# MainCircuit.net
KiCad netlist of a schematic drawn in Altium Designer
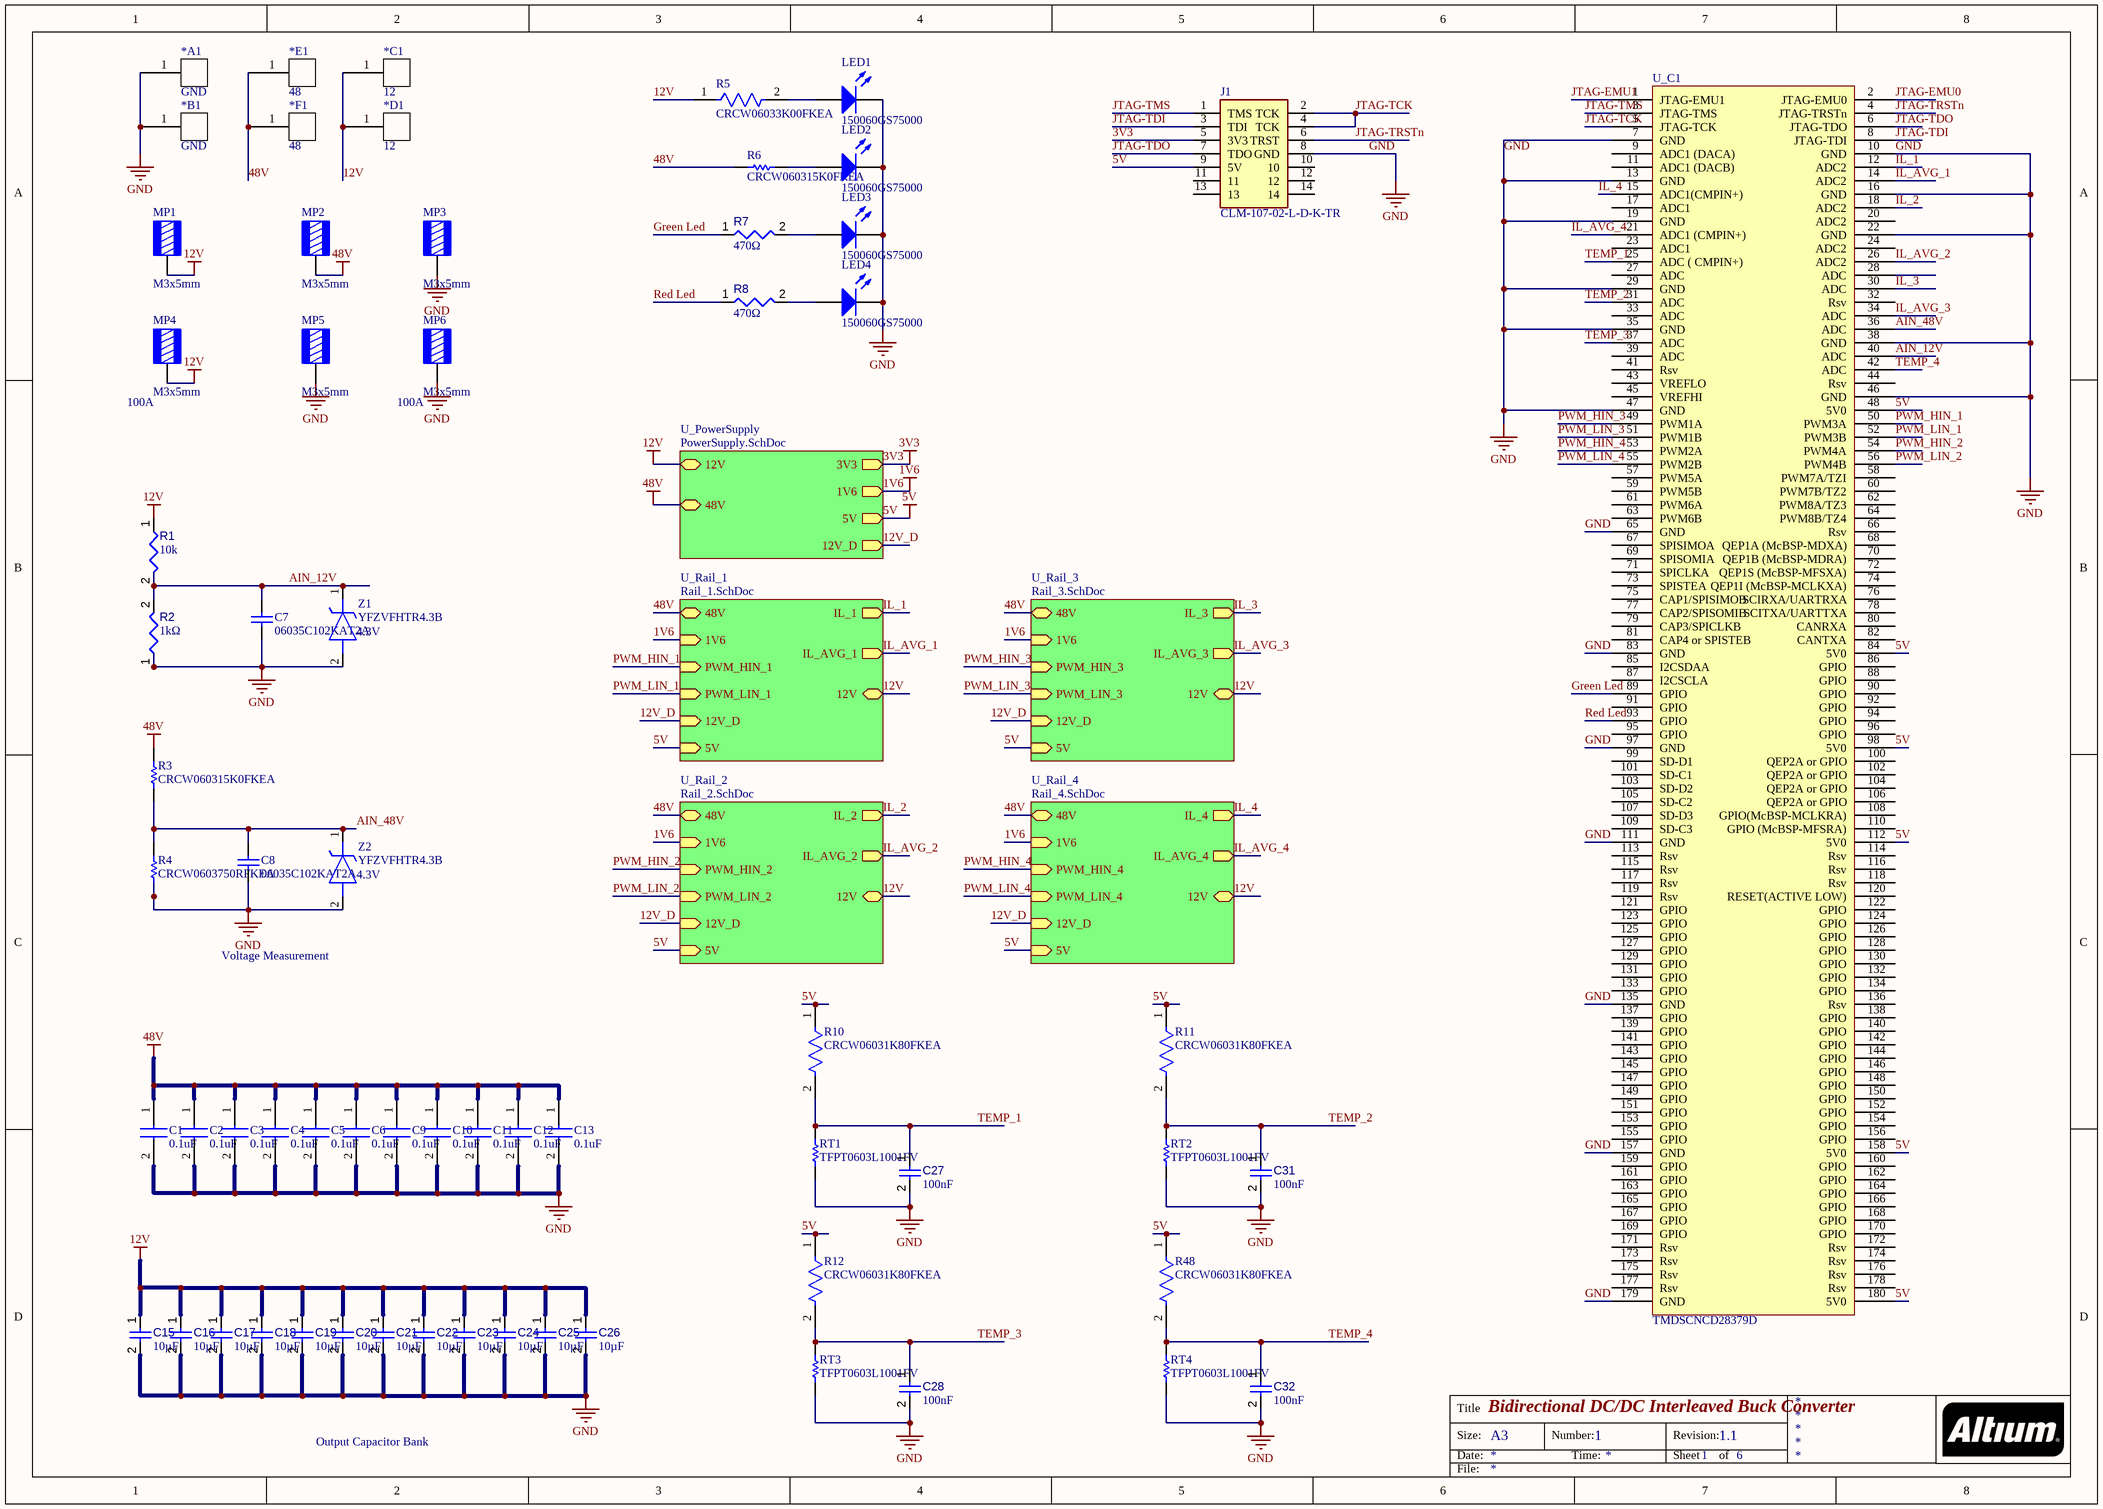
[diagram p0: MainCircuit.SchDoc]

(export (version "E")
  (design (tool "Eeschema 10.0.6"))
  (components
    (comp (ref "*A1")
      (value "GND")
      (description "Power Pad for Ground and Supply")
      (libsource (lib "University of Paderborn") (part "Power Pad"))
    )
    (comp (ref "*B1")
      (value "GND")
      (description "Power Pad for Ground and Supply")
      (libsource (lib "University of Paderborn") (part "Power Pad"))
    )
    (comp (ref "*C1")
      (value "12")
      (description "Power Pad for Ground and Supply")
      (libsource (lib "University of Paderborn") (part "Power Pad"))
    )
    (comp (ref "*D1")
      (value "12")
      (description "Power Pad for Ground and Supply")
      (libsource (lib "University of Paderborn") (part "Power Pad"))
    )
    (comp (ref "*E1")
      (value "48")
      (description "Power Pad for Ground and Supply")
      (libsource (lib "University of Paderborn") (part "Power Pad"))
    )
    (comp (ref "*F1")
      (value "48")
      (description "Power Pad for Ground and Supply")
      (libsource (lib "University of Paderborn") (part "Power Pad"))
    )
    (comp (ref "C1")
      (value "0.1uF")
      (footprint "SamacSys:CAPC1608X90N")
      (description "Capacitor")
      (fields
        (field (name "MANUFACTURER_PART_NUMBER") "06031C104K4T2A")
        (field (name "MOUSER PART NUMBER") "581-06031C104K4T2A")
      )
      (libsource (lib "*") (part "06031C104K4T2A"))
    )
    (comp (ref "C2")
      (value "0.1uF")
      (footprint "SamacSys:CAPC1608X90N")
      (description "Capacitor")
      (fields
        (field (name "MANUFACTURER_PART_NUMBER") "06031C104K4T2A")
        (field (name "MOUSER PART NUMBER") "581-06031C104K4T2A")
      )
      (libsource (lib "*") (part "06031C104K4T2A"))
    )
    (comp (ref "C3")
      (value "0.1uF")
      (footprint "SamacSys:CAPC1608X90N")
      (description "Capacitor")
      (fields
        (field (name "MANUFACTURER_PART_NUMBER") "06031C104K4T2A")
        (field (name "MOUSER PART NUMBER") "581-06031C104K4T2A")
      )
      (libsource (lib "*") (part "06031C104K4T2A"))
    )
    (comp (ref "C4")
      (value "0.1uF")
      (footprint "SamacSys:CAPC1608X90N")
      (description "Capacitor")
      (fields
        (field (name "MANUFACTURER_PART_NUMBER") "06031C104K4T2A")
        (field (name "MOUSER PART NUMBER") "581-06031C104K4T2A")
      )
      (libsource (lib "*") (part "06031C104K4T2A"))
    )
    (comp (ref "C5")
      (value "0.1uF")
      (footprint "SamacSys:CAPC1608X90N")
      (description "Capacitor")
      (fields
        (field (name "MANUFACTURER_PART_NUMBER") "06031C104K4T2A")
        (field (name "MOUSER PART NUMBER") "581-06031C104K4T2A")
      )
      (libsource (lib "*") (part "06031C104K4T2A"))
    )
    (comp (ref "C6")
      (value "0.1uF")
      (footprint "SamacSys:CAPC1608X90N")
      (description "Capacitor")
      (fields
        (field (name "MANUFACTURER_PART_NUMBER") "06031C104K4T2A")
        (field (name "MOUSER PART NUMBER") "581-06031C104K4T2A")
      )
      (libsource (lib "*") (part "06031C104K4T2A"))
    )
    (comp (ref "C7")
      (value "06035C102KAT2A")
      (footprint "CAPC1608X90X35LL15T15")
      (fields (field (name "MANUFACTURER") "AVX Interconnect / Elco"))
      (libsource (lib "Altium Content Vault") (part "CAP"))
    )
    (comp (ref "C8")
      (value "06035C102KAT2A")
      (footprint "CAPC1608X90X35LL15T15")
      (fields (field (name "MANUFACTURER") "AVX Interconnect / Elco"))
      (libsource (lib "Altium Content Vault") (part "CAP"))
    )
    (comp (ref "C9")
      (value "0.1uF")
      (footprint "SamacSys:CAPC1608X90N")
      (description "Capacitor")
      (fields
        (field (name "MANUFACTURER_PART_NUMBER") "06031C104K4T2A")
        (field (name "MOUSER PART NUMBER") "581-06031C104K4T2A")
      )
      (libsource (lib "*") (part "06031C104K4T2A"))
    )
    (comp (ref "C10")
      (value "0.1uF")
      (footprint "SamacSys:CAPC1608X90N")
      (description "Capacitor")
      (fields
        (field (name "MANUFACTURER_PART_NUMBER") "06031C104K4T2A")
        (field (name "MOUSER PART NUMBER") "581-06031C104K4T2A")
      )
      (libsource (lib "*") (part "06031C104K4T2A"))
    )
    (comp (ref "C11")
      (value "0.1uF")
      (footprint "SamacSys:CAPC1608X90N")
      (description "Capacitor")
      (fields
        (field (name "MANUFACTURER_PART_NUMBER") "06031C104K4T2A")
        (field (name "MOUSER PART NUMBER") "581-06031C104K4T2A")
      )
      (libsource (lib "*") (part "06031C104K4T2A"))
    )
    (comp (ref "C12")
      (value "0.1uF")
      (footprint "SamacSys:CAPC1608X90N")
      (description "Capacitor")
      (fields
        (field (name "MANUFACTURER_PART_NUMBER") "06031C104K4T2A")
        (field (name "MOUSER PART NUMBER") "581-06031C104K4T2A")
      )
      (libsource (lib "*") (part "06031C104K4T2A"))
    )
    (comp (ref "C13")
      (value "0.1uF")
      (footprint "SamacSys:CAPC1608X90N")
      (description "Capacitor")
      (fields
        (field (name "MANUFACTURER_PART_NUMBER") "06031C104K4T2A")
        (field (name "MOUSER PART NUMBER") "581-06031C104K4T2A")
      )
      (libsource (lib "*") (part "06031C104K4T2A"))
    )
    (comp (ref "C15")
      (value "10µF")
      (footprint "CAPC0805(2012)145_L")
      (description "Chip Capacitor, 10µF +/-20%, 25V, 0805, Thickness 1.45 mm")
      (fields (field (name "TOLERANCE") "10%") (field (name "Comment") "Capacitor 10µF +/-20% 25V 0805"))
      (libsource (lib "University of Paderborn") (part "CAP-NP-2"))
    )
    (comp (ref "C16")
      (value "10µF")
      (footprint "CAPC0805(2012)145_L")
      (description "Chip Capacitor, 10µF +/-20%, 25V, 0805, Thickness 1.45 mm")
      (fields (field (name "TOLERANCE") "10%") (field (name "Comment") "Capacitor 10µF +/-20% 25V 0805"))
      (libsource (lib "University of Paderborn") (part "CAP-NP-2"))
    )
    (comp (ref "C17")
      (value "10µF")
      (footprint "CAPC0805(2012)145_L")
      (description "Chip Capacitor, 10µF +/-20%, 25V, 0805, Thickness 1.45 mm")
      (fields (field (name "TOLERANCE") "10%") (field (name "Comment") "Capacitor 10µF +/-20% 25V 0805"))
      (libsource (lib "University of Paderborn") (part "CAP-NP-2"))
    )
    (comp (ref "C18")
      (value "10µF")
      (footprint "CAPC0805(2012)145_L")
      (description "Chip Capacitor, 10µF +/-20%, 25V, 0805, Thickness 1.45 mm")
      (fields (field (name "TOLERANCE") "10%") (field (name "Comment") "Capacitor 10µF +/-20% 25V 0805"))
      (libsource (lib "University of Paderborn") (part "CAP-NP-2"))
    )
    (comp (ref "C19")
      (value "10µF")
      (footprint "CAPC0805(2012)145_L")
      (description "Chip Capacitor, 10µF +/-20%, 25V, 0805, Thickness 1.45 mm")
      (fields (field (name "TOLERANCE") "10%") (field (name "Comment") "Capacitor 10µF +/-20% 25V 0805"))
      (libsource (lib "University of Paderborn") (part "CAP-NP-2"))
    )
    (comp (ref "C20")
      (value "10µF")
      (footprint "CAPC0805(2012)145_L")
      (description "Chip Capacitor, 10µF +/-20%, 25V, 0805, Thickness 1.45 mm")
      (fields (field (name "TOLERANCE") "10%") (field (name "Comment") "Capacitor 10µF +/-20% 25V 0805"))
      (libsource (lib "University of Paderborn") (part "CAP-NP-2"))
    )
    (comp (ref "C21")
      (value "10µF")
      (footprint "CAPC0805(2012)145_L")
      (description "Chip Capacitor, 10µF +/-20%, 25V, 0805, Thickness 1.45 mm")
      (fields (field (name "TOLERANCE") "10%") (field (name "Comment") "Capacitor 10µF +/-20% 25V 0805"))
      (libsource (lib "University of Paderborn") (part "CAP-NP-2"))
    )
    (comp (ref "C22")
      (value "10µF")
      (footprint "CAPC0805(2012)145_L")
      (description "Chip Capacitor, 10µF +/-20%, 25V, 0805, Thickness 1.45 mm")
      (fields (field (name "TOLERANCE") "10%") (field (name "Comment") "Capacitor 10µF +/-20% 25V 0805"))
      (libsource (lib "University of Paderborn") (part "CAP-NP-2"))
    )
    (comp (ref "C23")
      (value "10µF")
      (footprint "CAPC0805(2012)145_L")
      (description "Chip Capacitor, 10µF +/-20%, 25V, 0805, Thickness 1.45 mm")
      (fields (field (name "TOLERANCE") "10%") (field (name "Comment") "Capacitor 10µF +/-20% 25V 0805"))
      (libsource (lib "University of Paderborn") (part "CAP-NP-2"))
    )
    (comp (ref "C24")
      (value "10µF")
      (footprint "CAPC0805(2012)145_L")
      (description "Chip Capacitor, 10µF +/-20%, 25V, 0805, Thickness 1.45 mm")
      (fields (field (name "TOLERANCE") "10%") (field (name "Comment") "Capacitor 10µF +/-20% 25V 0805"))
      (libsource (lib "University of Paderborn") (part "CAP-NP-2"))
    )
    (comp (ref "C25")
      (value "10µF")
      (footprint "CAPC0805(2012)145_L")
      (description "Chip Capacitor, 10µF +/-20%, 25V, 0805, Thickness 1.45 mm")
      (fields (field (name "TOLERANCE") "10%") (field (name "Comment") "Capacitor 10µF +/-20% 25V 0805"))
      (libsource (lib "University of Paderborn") (part "CAP-NP-2"))
    )
    (comp (ref "C26")
      (value "10µF")
      (footprint "CAPC0805(2012)145_L")
      (description "Chip Capacitor, 10µF +/-20%, 25V, 0805, Thickness 1.45 mm")
      (fields (field (name "TOLERANCE") "10%") (field (name "Comment") "Capacitor 10µF +/-20% 25V 0805"))
      (libsource (lib "University of Paderborn") (part "CAP-NP-2"))
    )
    (comp (ref "C27")
      (value "100nF")
      (footprint "CAPC1608X90X40ML10T20")
      (description "Chip Capacitor, 100 nF, +/- 10%, 50 V, 0603 (1608 Metric)")
      (fields (field (name "TOLERANCE") "10%") (field (name "Comment") "Capacitor 100 nF +/-10% 50 V 0603"))
      (libsource (lib "University of Paderborn") (part "CAP-NP-2"))
    )
    (comp (ref "C28")
      (value "100nF")
      (footprint "CAPC1608X90X40ML10T20")
      (description "Chip Capacitor, 100 nF, +/- 10%, 50 V, 0603 (1608 Metric)")
      (fields (field (name "TOLERANCE") "10%") (field (name "Comment") "Capacitor 100 nF +/-10% 50 V 0603"))
      (libsource (lib "University of Paderborn") (part "CAP-NP-2"))
    )
    (comp (ref "C31")
      (value "100nF")
      (footprint "CAPC1608X90X40ML10T20")
      (description "Chip Capacitor, 100 nF, +/- 10%, 50 V, 0603 (1608 Metric)")
      (fields (field (name "TOLERANCE") "10%") (field (name "Comment") "Capacitor 100 nF +/-10% 50 V 0603"))
      (libsource (lib "University of Paderborn") (part "CAP-NP-2"))
    )
    (comp (ref "C32")
      (value "100nF")
      (footprint "CAPC1608X90X40ML10T20")
      (description "Chip Capacitor, 100 nF, +/- 10%, 50 V, 0603 (1608 Metric)")
      (fields (field (name "TOLERANCE") "10%") (field (name "Comment") "Capacitor 100 nF +/-10% 50 V 0603"))
      (libsource (lib "University of Paderborn") (part "CAP-NP-2"))
    )
    (comp (ref "J1")
      (value "CLM-107-02-L-D-K-TR")
      (footprint "SamacSys:CLM-107-02-XX-D-Y-TR")
      (description "Connector")
      (fields (field (name "MOUSER PART NUMBER") "200-CLM10702LDKTR"))
      (libsource (lib "*") (part "CLM-107-02-L-D-K-TR"))
    )
    (comp (ref "LED1")
      (value "150060GS75000")
      (footprint "0603_A")
      (description "SMD mono-color Chip LED, WL-SMCW, Green")
      (fields (field (name "MANUFACTURER") "Wuerth Elektronik"))
      (libsource (lib "Altium Content Vault") (part "WE-LED_K1A2-2"))
    )
    (comp (ref "LED2")
      (value "150060GS75000")
      (footprint "0603_A")
      (description "SMD mono-color Chip LED, WL-SMCW, Green")
      (fields (field (name "MANUFACTURER") "Wuerth Elektronik"))
      (libsource (lib "Altium Content Vault") (part "WE-LED_K1A2-2"))
    )
    (comp (ref "LED3")
      (value "150060GS75000")
      (footprint "0603_A")
      (description "SMD mono-color Chip LED, WL-SMCW, Green")
      (fields (field (name "MANUFACTURER") "Wuerth Elektronik"))
      (libsource (lib "Altium Content Vault") (part "WE-LED_K1A2-2"))
    )
    (comp (ref "LED4")
      (value "150060GS75000")
      (footprint "0603_A")
      (description "SMD mono-color Chip LED, WL-SMCW, Green")
      (fields (field (name "MANUFACTURER") "Wuerth Elektronik"))
      (libsource (lib "Altium Content Vault") (part "WE-LED_K1A2-2"))
    )
    (comp (ref "MP1")
      (value "M3x5mm")
      (footprint "7461057_for chemical surfaces")
      (description "WP-BUTR Press-Fit with Internal thread, two rows, 7x7mm, 6 pins, M3x5mm, 100A")
      (fields (field (name "PART NUMBER") "7461057") (field (name "PUBLISHER") "Wurth Elektronik"))
      (libsource (lib "Altium_WP-BUTR (rev19a)") (part "7461057"))
    )
    (comp (ref "MP2")
      (value "M3x5mm")
      (footprint "7461057_for chemical surfaces")
      (description "WP-BUTR Press-Fit with Internal thread, two rows, 7x7mm, 6 pins, M3x5mm, 100A")
      (fields (field (name "PART NUMBER") "7461057") (field (name "PUBLISHER") "Wurth Elektronik"))
      (libsource (lib "Altium_WP-BUTR (rev19a)") (part "7461057"))
    )
    (comp (ref "MP3")
      (value "M3x5mm")
      (footprint "7461057_for chemical surfaces")
      (description "WP-BUTR Press-Fit with Internal thread, two rows, 7x7mm, 6 pins, M3x5mm, 100A")
      (fields (field (name "PART NUMBER") "7461057") (field (name "PUBLISHER") "Wurth Elektronik"))
      (libsource (lib "Altium_WP-BUTR (rev19a)") (part "7461057"))
    )
    (comp (ref "MP4")
      (value "M3x5mm")
      (footprint "7461057_for chemical surfaces")
      (description "WP-BUTR Press-Fit with Internal thread, two rows, 7x7mm, 6 pins, M3x5mm, 100A")
      (fields (field (name "PART NUMBER") "7461057") (field (name "PUBLISHER") "Wurth Elektronik"))
      (libsource (lib "Altium_WP-BUTR (rev19a)") (part "7461057"))
    )
    (comp (ref "MP5")
      (value "M3x5mm")
      (footprint "7461057_for chemical surfaces")
      (description "WP-BUTR Press-Fit with Internal thread, two rows, 7x7mm, 6 pins, M3x5mm, 100A")
      (fields (field (name "PART NUMBER") "7461057") (field (name "PUBLISHER") "Wurth Elektronik"))
      (libsource (lib "Altium_WP-BUTR (rev19a)") (part "7461057"))
    )
    (comp (ref "MP6")
      (value "M3x5mm")
      (footprint "7461057_for chemical surfaces")
      (description "WP-BUTR Press-Fit with Internal thread, two rows, 7x7mm, 6 pins, M3x5mm, 100A")
      (fields (field (name "PART NUMBER") "7461057") (field (name "PUBLISHER") "Wurth Elektronik"))
      (libsource (lib "Altium_WP-BUTR (rev19a)") (part "7461057"))
    )
    (comp (ref "R1")
      (value "10k")
      (footprint "RESC2013X50X35ML15T15")
      (description "Chip Resistor, 10 KOhm, +/- 1%, 125 mW, -55 to 155 degC, 0805 (2012 Metric)")
      (fields (field (name "POWER") "125mW") (field (name "TOLERANCE") "1%"))
      (libsource (lib "University of Paderborn") (part "RES-2"))
    )
    (comp (ref "R2")
      (value "1kΩ")
      (footprint "RESC0805(2012)_L")
      (description "1K 0.125W 5% 0805 (2012 Metric)  SMD")
      (fields (field (name "POWER") "0.125W") (field (name "TOLERANCE") "5%"))
      (libsource (lib "University of Paderborn") (part "1KR5J"))
    )
    (comp (ref "R3")
      (value "CRCW060315K0FKEA")
      (footprint "RESC1609X50X30ML10T20")
      (fields (field (name "MANUFACTURER") "Vishay Dale"))
      (libsource (lib "Altium Content Vault") (part "RES"))
    )
    (comp (ref "R4")
      (value "CRCW0603750RFKEA")
      (footprint "RESC1609X50X30LL10T20")
      (fields (field (name "MANUFACTURER") "Vishay Dale"))
      (libsource (lib "Altium Content Vault") (part "RES"))
    )
    (comp (ref "R5")
      (value "CRCW06033K00FKEA")
      (footprint "FP-CRCW0603-e3-MFG")
      (description "RES Thick Film, 3kΩ, 1%, 0.1W, 100ppm/°C, 0603")
      (fields (field (name "TOLERANCE") "1%"))
      (libsource (lib "Altium Content Vault") (part "1029c3af85768c4190bb7ad29bc67b5"))
    )
    (comp (ref "R6")
      (value "CRCW060315K0FKEA")
      (footprint "RESC1609X50X30ML10T20")
      (fields (field (name "MANUFACTURER") "Vishay Dale"))
      (libsource (lib "Altium Content Vault") (part "RES"))
    )
    (comp (ref "R7")
      (value "470Ω")
      (footprint "RESC0805(2012)_L")
      (description "470R 0.125W 5% 0805 (2012 Metric)  SMD")
      (fields (field (name "POWER") "0.125W") (field (name "TOLERANCE") "5%"))
      (libsource (lib "University of Paderborn") (part "470R5J"))
    )
    (comp (ref "R8")
      (value "470Ω")
      (footprint "RESC0805(2012)_L")
      (description "470R 0.125W 5% 0805 (2012 Metric)  SMD")
      (fields (field (name "POWER") "0.125W") (field (name "TOLERANCE") "5%"))
      (libsource (lib "University of Paderborn") (part "470R5J"))
    )
    (comp (ref "R10")
      (value "CRCW06031K80FKEA")
      (footprint "FP-CRCW0603-e3-IPC_A")
      (description "RES Thick Film, 1.8kΩ, 1%, 0.1W, 100ppm/°C, 0603")
      (fields (field (name "TOLERANCE") "1%"))
      (libsource (lib "Altium Content Vault") (part "1029c3af85768c4190bb7ad29bc67b5"))
    )
    (comp (ref "R11")
      (value "CRCW06031K80FKEA")
      (footprint "FP-CRCW0603-e3-IPC_A")
      (description "RES Thick Film, 1.8kΩ, 1%, 0.1W, 100ppm/°C, 0603")
      (fields (field (name "TOLERANCE") "1%"))
      (libsource (lib "Altium Content Vault") (part "1029c3af85768c4190bb7ad29bc67b5"))
    )
    (comp (ref "R12")
      (value "CRCW06031K80FKEA")
      (footprint "FP-CRCW0603-e3-IPC_A")
      (description "RES Thick Film, 1.8kΩ, 1%, 0.1W, 100ppm/°C, 0603")
      (fields (field (name "TOLERANCE") "1%"))
      (libsource (lib "Altium Content Vault") (part "1029c3af85768c4190bb7ad29bc67b5"))
    )
    (comp (ref "R48")
      (value "CRCW06031K80FKEA")
      (footprint "FP-CRCW0603-e3-IPC_A")
      (description "RES Thick Film, 1.8kΩ, 1%, 0.1W, 100ppm/°C, 0603")
      (fields (field (name "TOLERANCE") "1%"))
      (libsource (lib "Altium Content Vault") (part "1029c3af85768c4190bb7ad29bc67b5"))
    )
    (comp (ref "RT1")
      (value "TFPT0603L1001FV")
      (footprint "RESC1609X55X30ML10T20")
      (fields (field (name "MANUFACTURER") "Vishay Dale"))
      (libsource (lib "Altium Content Vault") (part "RES"))
    )
    (comp (ref "RT2")
      (value "TFPT0603L1001FV")
      (footprint "RESC1609X55X30ML10T20")
      (fields (field (name "MANUFACTURER") "Vishay Dale"))
      (libsource (lib "Altium Content Vault") (part "RES"))
    )
    (comp (ref "RT3")
      (value "TFPT0603L1001FV")
      (footprint "RESC1609X55X30ML10T20")
      (fields (field (name "MANUFACTURER") "Vishay Dale"))
      (libsource (lib "Altium Content Vault") (part "RES"))
    )
    (comp (ref "RT4")
      (value "TFPT0603L1001FV")
      (footprint "RESC1609X55X30ML10T20")
      (fields (field (name "MANUFACTURER") "Vishay Dale"))
      (libsource (lib "Altium Content Vault") (part "RES"))
    )
    (comp (ref "U_C1")
      (value "TMDSCNCD28379D")
      (footprint "TMDSCNCD28379D-Footprint-1")
      (description "F28379D CONTROLCARD FOR C2000 RE")
      (libsource (lib "University of Paderborn") (part "TMDSCNCD28379D"))
    )
    (comp (ref "Z1")
      (value "YFZVFHTR4.3B")
      (footprint "SamacSys:YFZVFHTR43B")
      (description "Zener Diode")
      (fields (field (name "MOUSER PART NUMBER") "755-YFZVFHTR4.3B"))
      (libsource (lib "*") (part "YFZVFHTR4.3B"))
    )
    (comp (ref "Z2")
      (value "YFZVFHTR4.3B")
      (footprint "SamacSys:YFZVFHTR43B")
      (description "Zener Diode")
      (fields (field (name "MOUSER PART NUMBER") "755-YFZVFHTR4.3B"))
      (libsource (lib "*") (part "YFZVFHTR4.3B"))
    )
  )
  (nets
    (net (code "2") (name "/AIN_12V") (class "Default")
      (node (ref "C7") (pin "2") (pinfunction "2_2") (pintype "passive"))
      (node (ref "R1") (pin "2") (pinfunction "2_2") (pintype "passive"))
      (node (ref "R2") (pin "2") (pinfunction "2_2") (pintype "passive"))
      (node (ref "U_C1") (pin "40") (pinfunction "ADC_40") (pintype "passive"))
      (node (ref "Z1") (pin "1") (pinfunction "K_1") (pintype "passive"))
    )
    (net (code "3") (name "/AIN_48V") (class "Default")
      (node (ref "C8") (pin "2") (pinfunction "2_2") (pintype "passive"))
      (node (ref "R3") (pin "1") (pinfunction "1_1") (pintype "passive"))
      (node (ref "R4") (pin "2") (pinfunction "2_2") (pintype "passive"))
      (node (ref "U_C1") (pin "36") (pinfunction "ADC_36") (pintype "passive"))
      (node (ref "Z2") (pin "1") (pinfunction "K_1") (pintype "passive"))
    )
    (net (code "4") (name "/Green Led") (class "Default")
      (node (ref "R7") (pin "1") (pinfunction "1_1") (pintype "passive"))
      (node (ref "U_C1") (pin "89") (pinfunction "GPIO_89") (pintype "passive"))
    )
    (net (code "5") (name "/IL_1") (class "Default")
      (node (ref "U_C1") (pin "12") (pinfunction "ADC2_12") (pintype "passive"))
    )
    (net (code "6") (name "/IL_2") (class "Default")
      (node (ref "U_C1") (pin "18") (pinfunction "ADC2_18") (pintype "passive"))
    )
    (net (code "7") (name "/IL_3") (class "Default")
      (node (ref "U_C1") (pin "30") (pinfunction "ADC_30") (pintype "passive"))
    )
    (net (code "8") (name "/IL_4") (class "Default")
      (node (ref "U_C1") (pin "15") (pinfunction "ADC1(CMPIN+)_15") (pintype "passive"))
    )
    (net (code "9") (name "/IL_AVG_1") (class "Default")
      (node (ref "U_C1") (pin "14") (pinfunction "ADC2_14") (pintype "passive"))
    )
    (net (code "10") (name "/IL_AVG_2") (class "Default")
      (node (ref "U_C1") (pin "26") (pinfunction "ADC2_26") (pintype "passive"))
    )
    (net (code "11") (name "/IL_AVG_3") (class "Default")
      (node (ref "U_C1") (pin "34") (pinfunction "ADC_34") (pintype "passive"))
    )
    (net (code "12") (name "/IL_AVG_4") (class "Default")
      (node (ref "U_C1") (pin "21") (pinfunction "ADC1_(CMPIN+)_21") (pintype "passive"))
    )
    (net (code "13") (name "/JTAG-EMU0") (class "Default")
      (node (ref "U_C1") (pin "2") (pinfunction "JTAG-EMU0_2") (pintype "passive"))
    )
    (net (code "14") (name "/JTAG-EMU1") (class "Default")
      (node (ref "U_C1") (pin "1") (pinfunction "JTAG-EMU1_1") (pintype "passive"))
    )
    (net (code "15") (name "/JTAG-TCK") (class "Default")
      (node (ref "J1") (pin "2") (pinfunction "TCK_2") (pintype "passive"))
      (node (ref "J1") (pin "4") (pinfunction "TCK_4") (pintype "passive"))
      (node (ref "U_C1") (pin "5") (pinfunction "JTAG-TCK_5") (pintype "passive"))
    )
    (net (code "16") (name "/JTAG-TDI") (class "Default")
      (node (ref "J1") (pin "3") (pinfunction "TDI_3") (pintype "passive"))
      (node (ref "U_C1") (pin "8") (pinfunction "JTAG-TDI_8") (pintype "passive"))
    )
    (net (code "17") (name "/JTAG-TDO") (class "Default")
      (node (ref "J1") (pin "7") (pinfunction "TDO_7") (pintype "passive"))
      (node (ref "U_C1") (pin "6") (pinfunction "JTAG-TDO_6") (pintype "passive"))
    )
    (net (code "18") (name "/JTAG-TMS") (class "Default")
      (node (ref "J1") (pin "1") (pinfunction "TMS_1") (pintype "passive"))
      (node (ref "U_C1") (pin "3") (pinfunction "JTAG-TMS_3") (pintype "passive"))
    )
    (net (code "19") (name "/JTAG-TRSTn") (class "Default")
      (node (ref "J1") (pin "6") (pinfunction "TRST_6") (pintype "passive"))
      (node (ref "U_C1") (pin "4") (pinfunction "JTAG-TRSTn_4") (pintype "passive"))
    )
    (net (code "20") (name "/PWM_HIN_1") (class "Default")
      (node (ref "U_C1") (pin "50") (pinfunction "PWM3A_50") (pintype "passive"))
    )
    (net (code "21") (name "/PWM_HIN_2") (class "Default")
      (node (ref "U_C1") (pin "54") (pinfunction "PWM4A_54") (pintype "passive"))
    )
    (net (code "22") (name "/PWM_HIN_3") (class "Default")
      (node (ref "U_C1") (pin "49") (pinfunction "PWM1A_49") (pintype "passive"))
    )
    (net (code "23") (name "/PWM_HIN_4") (class "Default")
      (node (ref "U_C1") (pin "53") (pinfunction "PWM2A_53") (pintype "passive"))
    )
    (net (code "24") (name "/PWM_LIN_1") (class "Default")
      (node (ref "U_C1") (pin "52") (pinfunction "PWM3B_52") (pintype "passive"))
    )
    (net (code "25") (name "/PWM_LIN_2") (class "Default")
      (node (ref "U_C1") (pin "56") (pinfunction "PWM4B_56") (pintype "passive"))
    )
    (net (code "26") (name "/PWM_LIN_3") (class "Default")
      (node (ref "U_C1") (pin "51") (pinfunction "PWM1B_51") (pintype "passive"))
    )
    (net (code "27") (name "/PWM_LIN_4") (class "Default")
      (node (ref "U_C1") (pin "55") (pinfunction "PWM2B_55") (pintype "passive"))
    )
    (net (code "28") (name "/Red Led") (class "Default")
      (node (ref "R8") (pin "1") (pinfunction "1_1") (pintype "passive"))
      (node (ref "U_C1") (pin "93") (pinfunction "GPIO_93") (pintype "passive"))
    )
    (net (code "29") (name "/TEMP_1") (class "Default")
      (node (ref "C27") (pin "1") (pinfunction "1_1") (pintype "passive"))
      (node (ref "R10") (pin "2") (pinfunction "2_2") (pintype "passive"))
      (node (ref "RT1") (pin "1") (pinfunction "1_1") (pintype "passive"))
      (node (ref "U_C1") (pin "25") (pinfunction "ADC_(_CMPIN+)_25") (pintype "passive"))
    )
    (net (code "30") (name "/TEMP_2") (class "Default")
      (node (ref "C31") (pin "1") (pinfunction "1_1") (pintype "passive"))
      (node (ref "R11") (pin "2") (pinfunction "2_2") (pintype "passive"))
      (node (ref "RT2") (pin "1") (pinfunction "1_1") (pintype "passive"))
      (node (ref "U_C1") (pin "31") (pinfunction "ADC_31") (pintype "passive"))
    )
    (net (code "31") (name "/TEMP_3") (class "Default")
      (node (ref "C28") (pin "1") (pinfunction "1_1") (pintype "passive"))
      (node (ref "R12") (pin "2") (pinfunction "2_2") (pintype "passive"))
      (node (ref "RT3") (pin "1") (pinfunction "1_1") (pintype "passive"))
      (node (ref "U_C1") (pin "37") (pinfunction "ADC_37") (pintype "passive"))
    )
    (net (code "32") (name "/TEMP_4") (class "Default")
      (node (ref "C32") (pin "1") (pinfunction "1_1") (pintype "passive"))
      (node (ref "R48") (pin "2") (pinfunction "2_2") (pintype "passive"))
      (node (ref "RT4") (pin "1") (pinfunction "1_1") (pintype "passive"))
      (node (ref "U_C1") (pin "42") (pinfunction "ADC_42") (pintype "passive"))
    )
    (net (code "34") (name "3V3") (class "Default")
      (node (ref "J1") (pin "5") (pinfunction "3V3_5") (pintype "passive"))
    )
    (net (code "35") (name "5V") (class "Default")
      (node (ref "J1") (pin "9") (pinfunction "5V_9") (pintype "passive"))
      (node (ref "R10") (pin "1") (pinfunction "1_1") (pintype "passive"))
      (node (ref "R11") (pin "1") (pinfunction "1_1") (pintype "passive"))
      (node (ref "R12") (pin "1") (pinfunction "1_1") (pintype "passive"))
      (node (ref "R48") (pin "1") (pinfunction "1_1") (pintype "passive"))
      (node (ref "U_C1") (pin "112") (pinfunction "5V0_112") (pintype "passive"))
      (node (ref "U_C1") (pin "158") (pinfunction "5V0_158") (pintype "passive"))
      (node (ref "U_C1") (pin "180") (pinfunction "5V0_180") (pintype "passive"))
      (node (ref "U_C1") (pin "48") (pinfunction "5V0_48") (pintype "passive"))
      (node (ref "U_C1") (pin "84") (pinfunction "5V0_84") (pintype "passive"))
      (node (ref "U_C1") (pin "98") (pinfunction "5V0_98") (pintype "passive"))
    )
    (net (code "36") (name "12V") (class "Default")
      (node (ref "*C1") (pin "1") (pinfunction "1_1") (pintype "passive"))
      (node (ref "*D1") (pin "1") (pinfunction "1_1") (pintype "passive"))
      (node (ref "C15") (pin "1") (pinfunction "1_1") (pintype "passive"))
      (node (ref "C16") (pin "1") (pinfunction "1_1") (pintype "passive"))
      (node (ref "C17") (pin "1") (pinfunction "1_1") (pintype "passive"))
      (node (ref "C18") (pin "1") (pinfunction "1_1") (pintype "passive"))
      (node (ref "C19") (pin "1") (pinfunction "1_1") (pintype "passive"))
      (node (ref "C20") (pin "1") (pinfunction "1_1") (pintype "passive"))
      (node (ref "C21") (pin "1") (pinfunction "1_1") (pintype "passive"))
      (node (ref "C22") (pin "1") (pinfunction "1_1") (pintype "passive"))
      (node (ref "C23") (pin "1") (pinfunction "1_1") (pintype "passive"))
      (node (ref "C24") (pin "1") (pinfunction "1_1") (pintype "passive"))
      (node (ref "C25") (pin "1") (pinfunction "1_1") (pintype "passive"))
      (node (ref "C26") (pin "1") (pinfunction "1_1") (pintype "passive"))
      (node (ref "MP1") (pin "1") (pinfunction "1_1") (pintype "passive"))
      (node (ref "MP4") (pin "1") (pinfunction "1_1") (pintype "passive"))
      (node (ref "R1") (pin "1") (pinfunction "1_1") (pintype "passive"))
      (node (ref "R5") (pin "1") (pinfunction "1_1") (pintype "passive"))
    )
    (net (code "37") (name "48V") (class "Default")
      (node (ref "*E1") (pin "1") (pinfunction "1_1") (pintype "passive"))
      (node (ref "*F1") (pin "1") (pinfunction "1_1") (pintype "passive"))
      (node (ref "C1") (pin "1") (pinfunction "1_1") (pintype "passive"))
      (node (ref "C10") (pin "1") (pinfunction "1_1") (pintype "passive"))
      (node (ref "C11") (pin "1") (pinfunction "1_1") (pintype "passive"))
      (node (ref "C12") (pin "1") (pinfunction "1_1") (pintype "passive"))
      (node (ref "C13") (pin "1") (pinfunction "1_1") (pintype "passive"))
      (node (ref "C2") (pin "1") (pinfunction "1_1") (pintype "passive"))
      (node (ref "C3") (pin "1") (pinfunction "1_1") (pintype "passive"))
      (node (ref "C4") (pin "1") (pinfunction "1_1") (pintype "passive"))
      (node (ref "C5") (pin "1") (pinfunction "1_1") (pintype "passive"))
      (node (ref "C6") (pin "1") (pinfunction "1_1") (pintype "passive"))
      (node (ref "C9") (pin "1") (pinfunction "1_1") (pintype "passive"))
      (node (ref "MP2") (pin "1") (pinfunction "1_1") (pintype "passive"))
      (node (ref "R3") (pin "2") (pinfunction "2_2") (pintype "passive"))
      (node (ref "R6") (pin "1") (pinfunction "1_1") (pintype "passive"))
    )
    (net (code "38") (name "GND") (class "Default")
      (node (ref "*A1") (pin "1") (pinfunction "1_1") (pintype "passive"))
      (node (ref "*B1") (pin "1") (pinfunction "1_1") (pintype "passive"))
      (node (ref "C1") (pin "2") (pinfunction "2_2") (pintype "passive"))
      (node (ref "C10") (pin "2") (pinfunction "2_2") (pintype "passive"))
      (node (ref "C11") (pin "2") (pinfunction "2_2") (pintype "passive"))
      (node (ref "C12") (pin "2") (pinfunction "2_2") (pintype "passive"))
      (node (ref "C13") (pin "2") (pinfunction "2_2") (pintype "passive"))
      (node (ref "C15") (pin "2") (pinfunction "2_2") (pintype "passive"))
      (node (ref "C16") (pin "2") (pinfunction "2_2") (pintype "passive"))
      (node (ref "C17") (pin "2") (pinfunction "2_2") (pintype "passive"))
      (node (ref "C18") (pin "2") (pinfunction "2_2") (pintype "passive"))
      (node (ref "C19") (pin "2") (pinfunction "2_2") (pintype "passive"))
      (node (ref "C2") (pin "2") (pinfunction "2_2") (pintype "passive"))
      (node (ref "C20") (pin "2") (pinfunction "2_2") (pintype "passive"))
      (node (ref "C21") (pin "2") (pinfunction "2_2") (pintype "passive"))
      (node (ref "C22") (pin "2") (pinfunction "2_2") (pintype "passive"))
      (node (ref "C23") (pin "2") (pinfunction "2_2") (pintype "passive"))
      (node (ref "C24") (pin "2") (pinfunction "2_2") (pintype "passive"))
      (node (ref "C25") (pin "2") (pinfunction "2_2") (pintype "passive"))
      (node (ref "C26") (pin "2") (pinfunction "2_2") (pintype "passive"))
      (node (ref "C27") (pin "2") (pinfunction "2_2") (pintype "passive"))
      (node (ref "C28") (pin "2") (pinfunction "2_2") (pintype "passive"))
      (node (ref "C3") (pin "2") (pinfunction "2_2") (pintype "passive"))
      (node (ref "C31") (pin "2") (pinfunction "2_2") (pintype "passive"))
      (node (ref "C32") (pin "2") (pinfunction "2_2") (pintype "passive"))
      (node (ref "C4") (pin "2") (pinfunction "2_2") (pintype "passive"))
      (node (ref "C5") (pin "2") (pinfunction "2_2") (pintype "passive"))
      (node (ref "C6") (pin "2") (pinfunction "2_2") (pintype "passive"))
      (node (ref "C7") (pin "1") (pinfunction "1_1") (pintype "passive"))
      (node (ref "C8") (pin "1") (pinfunction "1_1") (pintype "passive"))
      (node (ref "C9") (pin "2") (pinfunction "2_2") (pintype "passive"))
      (node (ref "J1") (pin "8") (pinfunction "GND_8") (pintype "passive"))
      (node (ref "LED1") (pin "1") (pinfunction "K_1") (pintype "passive"))
      (node (ref "LED2") (pin "1") (pinfunction "K_1") (pintype "passive"))
      (node (ref "LED3") (pin "1") (pinfunction "K_1") (pintype "passive"))
      (node (ref "LED4") (pin "1") (pinfunction "K_1") (pintype "passive"))
      (node (ref "MP3") (pin "1") (pinfunction "1_1") (pintype "passive"))
      (node (ref "MP5") (pin "1") (pinfunction "1_1") (pintype "passive"))
      (node (ref "MP6") (pin "1") (pinfunction "1_1") (pintype "passive"))
      (node (ref "R2") (pin "1") (pinfunction "1_1") (pintype "passive"))
      (node (ref "R4") (pin "1") (pinfunction "1_1") (pintype "passive"))
      (node (ref "RT1") (pin "2") (pinfunction "2_2") (pintype "passive"))
      (node (ref "RT2") (pin "2") (pinfunction "2_2") (pintype "passive"))
      (node (ref "RT3") (pin "2") (pinfunction "2_2") (pintype "passive"))
      (node (ref "RT4") (pin "2") (pinfunction "2_2") (pintype "passive"))
      (node (ref "U_C1") (pin "10") (pinfunction "GND_10") (pintype "passive"))
      (node (ref "U_C1") (pin "111") (pinfunction "GND_111") (pintype "passive"))
      (node (ref "U_C1") (pin "13") (pinfunction "GND_13") (pintype "passive"))
      (node (ref "U_C1") (pin "135") (pinfunction "GND_135") (pintype "passive"))
      (node (ref "U_C1") (pin "157") (pinfunction "GND_157") (pintype "passive"))
      (node (ref "U_C1") (pin "16") (pinfunction "GND_16") (pintype "passive"))
      (node (ref "U_C1") (pin "179") (pinfunction "GND_179") (pintype "passive"))
      (node (ref "U_C1") (pin "19") (pinfunction "GND_19") (pintype "passive"))
      (node (ref "U_C1") (pin "22") (pinfunction "GND_22") (pintype "passive"))
      (node (ref "U_C1") (pin "29") (pinfunction "GND_29") (pintype "passive"))
      (node (ref "U_C1") (pin "35") (pinfunction "GND_35") (pintype "passive"))
      (node (ref "U_C1") (pin "38") (pinfunction "GND_38") (pintype "passive"))
      (node (ref "U_C1") (pin "46") (pinfunction "GND_46") (pintype "passive"))
      (node (ref "U_C1") (pin "47") (pinfunction "GND_47") (pintype "passive"))
      (node (ref "U_C1") (pin "65") (pinfunction "GND_65") (pintype "passive"))
      (node (ref "U_C1") (pin "7") (pinfunction "GND_7") (pintype "passive"))
      (node (ref "U_C1") (pin "83") (pinfunction "GND_83") (pintype "passive"))
      (node (ref "U_C1") (pin "97") (pinfunction "GND_97") (pintype "passive"))
      (node (ref "Z1") (pin "2") (pinfunction "A_2") (pintype "passive"))
      (node (ref "Z2") (pin "2") (pinfunction "A_2") (pintype "passive"))
    )
    (net (code "39") (name "Net-(LED1-A)") (class "Default")
      (node (ref "LED1") (pin "2") (pinfunction "A_2") (pintype "passive"))
      (node (ref "R5") (pin "2") (pinfunction "2_2") (pintype "passive"))
    )
    (net (code "40") (name "Net-(LED2-A)") (class "Default")
      (node (ref "LED2") (pin "2") (pinfunction "A_2") (pintype "passive"))
      (node (ref "R6") (pin "2") (pinfunction "2_2") (pintype "passive"))
    )
    (net (code "41") (name "Net-(LED3-A)") (class "Default")
      (node (ref "LED3") (pin "2") (pinfunction "A_2") (pintype "passive"))
      (node (ref "R7") (pin "2") (pinfunction "2_2") (pintype "passive"))
    )
    (net (code "42") (name "Net-(LED4-A)") (class "Default")
      (node (ref "LED4") (pin "2") (pinfunction "A_2") (pintype "passive"))
      (node (ref "R8") (pin "2") (pinfunction "2_2") (pintype "passive"))
    )
    (net (code "43") (name "unconnected-(J1-Pad10)") (class "Default")
      (node (ref "J1") (pin "10") (pinfunction "10_10") (pintype "passive"))
    )
    (net (code "44") (name "unconnected-(J1-Pad11)") (class "Default")
      (node (ref "J1") (pin "11") (pinfunction "11_11") (pintype "passive"))
    )
    (net (code "45") (name "unconnected-(J1-Pad12)") (class "Default")
      (node (ref "J1") (pin "12") (pinfunction "12_12") (pintype "passive"))
    )
    (net (code "46") (name "unconnected-(J1-Pad13)") (class "Default")
      (node (ref "J1") (pin "13") (pinfunction "13_13") (pintype "passive"))
    )
    (net (code "47") (name "unconnected-(J1-Pad14)") (class "Default")
      (node (ref "J1") (pin "14") (pinfunction "14_14") (pintype "passive"))
    )
    (net (code "48") (name "unconnected-(U_C1-ADC-Pad27)") (class "Default")
      (node (ref "U_C1") (pin "27") (pinfunction "ADC_27") (pintype "passive"))
    )
    (net (code "49") (name "unconnected-(U_C1-ADC-Pad28)") (class "Default")
      (node (ref "U_C1") (pin "28") (pinfunction "ADC_28") (pintype "passive"))
    )
    (net (code "50") (name "unconnected-(U_C1-ADC-Pad33)") (class "Default")
      (node (ref "U_C1") (pin "33") (pinfunction "ADC_33") (pintype "passive"))
    )
    (net (code "51") (name "unconnected-(U_C1-ADC-Pad39)") (class "Default")
      (node (ref "U_C1") (pin "39") (pinfunction "ADC_39") (pintype "passive"))
    )
    (net (code "52") (name "unconnected-(U_C1-ADC1-Pad17)") (class "Default")
      (node (ref "U_C1") (pin "17") (pinfunction "ADC1_17") (pintype "passive"))
    )
    (net (code "53") (name "unconnected-(U_C1-ADC1-Pad23)") (class "Default")
      (node (ref "U_C1") (pin "23") (pinfunction "ADC1_23") (pintype "passive"))
    )
    (net (code "54") (name "unconnected-(U_C1-ADC1_(DACA)-Pad9)") (class "Default")
      (node (ref "U_C1") (pin "9") (pinfunction "ADC1_(DACA)_9") (pintype "passive"))
    )
    (net (code "55") (name "unconnected-(U_C1-ADC1_(DACB)-Pad11)") (class "Default")
      (node (ref "U_C1") (pin "11") (pinfunction "ADC1_(DACB)_11") (pintype "passive"))
    )
    (net (code "56") (name "unconnected-(U_C1-ADC2-Pad20)") (class "Default")
      (node (ref "U_C1") (pin "20") (pinfunction "ADC2_20") (pintype "passive"))
    )
    (net (code "57") (name "unconnected-(U_C1-ADC2-Pad24)") (class "Default")
      (node (ref "U_C1") (pin "24") (pinfunction "ADC2_24") (pintype "passive"))
    )
    (net (code "58") (name "unconnected-(U_C1-CANRXA-Pad80)") (class "Default")
      (node (ref "U_C1") (pin "80") (pinfunction "CANRXA_80") (pintype "passive"))
    )
    (net (code "59") (name "unconnected-(U_C1-CANTXA-Pad82)") (class "Default")
      (node (ref "U_C1") (pin "82") (pinfunction "CANTXA_82") (pintype "passive"))
    )
    (net (code "60") (name "unconnected-(U_C1-CAP1{slash}SPISIMOB-Pad75)") (class "Default")
      (node (ref "U_C1") (pin "75") (pinfunction "CAP1/SPISIMOB_75") (pintype "passive"))
    )
    (net (code "61") (name "unconnected-(U_C1-CAP2{slash}SPISOMIB-Pad77)") (class "Default")
      (node (ref "U_C1") (pin "77") (pinfunction "CAP2/SPISOMIB_77") (pintype "passive"))
    )
    (net (code "62") (name "unconnected-(U_C1-CAP3{slash}SPICLKB-Pad79)") (class "Default")
      (node (ref "U_C1") (pin "79") (pinfunction "CAP3/SPICLKB_79") (pintype "passive"))
    )
    (net (code "63") (name "unconnected-(U_C1-CAP4_or_SPISTEB-Pad81)") (class "Default")
      (node (ref "U_C1") (pin "81") (pinfunction "CAP4_or_SPISTEB_81") (pintype "passive"))
    )
    (net (code "64") (name "unconnected-(U_C1-GPIO(McBSP-MCLKRA)-Pad108)") (class "Default")
      (node (ref "U_C1") (pin "108") (pinfunction "GPIO(McBSP-MCLKRA)_108") (pintype "passive"))
    )
    (net (code "65") (name "unconnected-(U_C1-GPIO-Pad86)") (class "Default")
      (node (ref "U_C1") (pin "86") (pinfunction "GPIO_86") (pintype "passive"))
    )
    (net (code "66") (name "unconnected-(U_C1-GPIO-Pad88)") (class "Default")
      (node (ref "U_C1") (pin "88") (pinfunction "GPIO_88") (pintype "passive"))
    )
    (net (code "67") (name "unconnected-(U_C1-GPIO-Pad90)") (class "Default")
      (node (ref "U_C1") (pin "90") (pinfunction "GPIO_90") (pintype "passive"))
    )
    (net (code "68") (name "unconnected-(U_C1-GPIO-Pad91)") (class "Default")
      (node (ref "U_C1") (pin "91") (pinfunction "GPIO_91") (pintype "passive"))
    )
    (net (code "69") (name "unconnected-(U_C1-GPIO-Pad92)") (class "Default")
      (node (ref "U_C1") (pin "92") (pinfunction "GPIO_92") (pintype "passive"))
    )
    (net (code "70") (name "unconnected-(U_C1-GPIO-Pad94)") (class "Default")
      (node (ref "U_C1") (pin "94") (pinfunction "GPIO_94") (pintype "passive"))
    )
    (net (code "71") (name "unconnected-(U_C1-GPIO-Pad95)") (class "Default")
      (node (ref "U_C1") (pin "95") (pinfunction "GPIO_95") (pintype "passive"))
    )
    (net (code "72") (name "unconnected-(U_C1-GPIO-Pad96)") (class "Default")
      (node (ref "U_C1") (pin "96") (pinfunction "GPIO_96") (pintype "passive"))
    )
    (net (code "73") (name "unconnected-(U_C1-GPIO-Pad121)") (class "Default")
      (node (ref "U_C1") (pin "121") (pinfunction "GPIO_121") (pintype "passive"))
    )
    (net (code "74") (name "unconnected-(U_C1-GPIO-Pad122)") (class "Default")
      (node (ref "U_C1") (pin "122") (pinfunction "GPIO_122") (pintype "passive"))
    )
    (net (code "75") (name "unconnected-(U_C1-GPIO-Pad123)") (class "Default")
      (node (ref "U_C1") (pin "123") (pinfunction "GPIO_123") (pintype "passive"))
    )
    (net (code "76") (name "unconnected-(U_C1-GPIO-Pad124)") (class "Default")
      (node (ref "U_C1") (pin "124") (pinfunction "GPIO_124") (pintype "passive"))
    )
    (net (code "77") (name "unconnected-(U_C1-GPIO-Pad125)") (class "Default")
      (node (ref "U_C1") (pin "125") (pinfunction "GPIO_125") (pintype "passive"))
    )
    (net (code "78") (name "unconnected-(U_C1-GPIO-Pad126)") (class "Default")
      (node (ref "U_C1") (pin "126") (pinfunction "GPIO_126") (pintype "passive"))
    )
    (net (code "79") (name "unconnected-(U_C1-GPIO-Pad127)") (class "Default")
      (node (ref "U_C1") (pin "127") (pinfunction "GPIO_127") (pintype "passive"))
    )
    (net (code "80") (name "unconnected-(U_C1-GPIO-Pad128)") (class "Default")
      (node (ref "U_C1") (pin "128") (pinfunction "GPIO_128") (pintype "passive"))
    )
    (net (code "81") (name "unconnected-(U_C1-GPIO-Pad129)") (class "Default")
      (node (ref "U_C1") (pin "129") (pinfunction "GPIO_129") (pintype "passive"))
    )
    (net (code "82") (name "unconnected-(U_C1-GPIO-Pad130)") (class "Default")
      (node (ref "U_C1") (pin "130") (pinfunction "GPIO_130") (pintype "passive"))
    )
    (net (code "83") (name "unconnected-(U_C1-GPIO-Pad131)") (class "Default")
      (node (ref "U_C1") (pin "131") (pinfunction "GPIO_131") (pintype "passive"))
    )
    (net (code "84") (name "unconnected-(U_C1-GPIO-Pad132)") (class "Default")
      (node (ref "U_C1") (pin "132") (pinfunction "GPIO_132") (pintype "passive"))
    )
    (net (code "85") (name "unconnected-(U_C1-GPIO-Pad133)") (class "Default")
      (node (ref "U_C1") (pin "133") (pinfunction "GPIO_133") (pintype "passive"))
    )
    (net (code "86") (name "unconnected-(U_C1-GPIO-Pad134)") (class "Default")
      (node (ref "U_C1") (pin "134") (pinfunction "GPIO_134") (pintype "passive"))
    )
    (net (code "87") (name "unconnected-(U_C1-GPIO-Pad137)") (class "Default")
      (node (ref "U_C1") (pin "137") (pinfunction "GPIO_137") (pintype "passive"))
    )
    (net (code "88") (name "unconnected-(U_C1-GPIO-Pad138)") (class "Default")
      (node (ref "U_C1") (pin "138") (pinfunction "GPIO_138") (pintype "passive"))
    )
    (net (code "89") (name "unconnected-(U_C1-GPIO-Pad139)") (class "Default")
      (node (ref "U_C1") (pin "139") (pinfunction "GPIO_139") (pintype "passive"))
    )
    (net (code "90") (name "unconnected-(U_C1-GPIO-Pad140)") (class "Default")
      (node (ref "U_C1") (pin "140") (pinfunction "GPIO_140") (pintype "passive"))
    )
    (net (code "91") (name "unconnected-(U_C1-GPIO-Pad141)") (class "Default")
      (node (ref "U_C1") (pin "141") (pinfunction "GPIO_141") (pintype "passive"))
    )
    (net (code "92") (name "unconnected-(U_C1-GPIO-Pad142)") (class "Default")
      (node (ref "U_C1") (pin "142") (pinfunction "GPIO_142") (pintype "passive"))
    )
    (net (code "93") (name "unconnected-(U_C1-GPIO-Pad143)") (class "Default")
      (node (ref "U_C1") (pin "143") (pinfunction "GPIO_143") (pintype "passive"))
    )
    (net (code "94") (name "unconnected-(U_C1-GPIO-Pad144)") (class "Default")
      (node (ref "U_C1") (pin "144") (pinfunction "GPIO_144") (pintype "passive"))
    )
    (net (code "95") (name "unconnected-(U_C1-GPIO-Pad145)") (class "Default")
      (node (ref "U_C1") (pin "145") (pinfunction "GPIO_145") (pintype "passive"))
    )
    (net (code "96") (name "unconnected-(U_C1-GPIO-Pad146)") (class "Default")
      (node (ref "U_C1") (pin "146") (pinfunction "GPIO_146") (pintype "passive"))
    )
    (net (code "97") (name "unconnected-(U_C1-GPIO-Pad147)") (class "Default")
      (node (ref "U_C1") (pin "147") (pinfunction "GPIO_147") (pintype "passive"))
    )
    (net (code "98") (name "unconnected-(U_C1-GPIO-Pad148)") (class "Default")
      (node (ref "U_C1") (pin "148") (pinfunction "GPIO_148") (pintype "passive"))
    )
    (net (code "99") (name "unconnected-(U_C1-GPIO-Pad149)") (class "Default")
      (node (ref "U_C1") (pin "149") (pinfunction "GPIO_149") (pintype "passive"))
    )
    (net (code "100") (name "unconnected-(U_C1-GPIO-Pad150)") (class "Default")
      (node (ref "U_C1") (pin "150") (pinfunction "GPIO_150") (pintype "passive"))
    )
    (net (code "101") (name "unconnected-(U_C1-GPIO-Pad151)") (class "Default")
      (node (ref "U_C1") (pin "151") (pinfunction "GPIO_151") (pintype "passive"))
    )
    (net (code "102") (name "unconnected-(U_C1-GPIO-Pad152)") (class "Default")
      (node (ref "U_C1") (pin "152") (pinfunction "GPIO_152") (pintype "passive"))
    )
    (net (code "103") (name "unconnected-(U_C1-GPIO-Pad153)") (class "Default")
      (node (ref "U_C1") (pin "153") (pinfunction "GPIO_153") (pintype "passive"))
    )
    (net (code "104") (name "unconnected-(U_C1-GPIO-Pad154)") (class "Default")
      (node (ref "U_C1") (pin "154") (pinfunction "GPIO_154") (pintype "passive"))
    )
    (net (code "105") (name "unconnected-(U_C1-GPIO-Pad155)") (class "Default")
      (node (ref "U_C1") (pin "155") (pinfunction "GPIO_155") (pintype "passive"))
    )
    (net (code "106") (name "unconnected-(U_C1-GPIO-Pad156)") (class "Default")
      (node (ref "U_C1") (pin "156") (pinfunction "GPIO_156") (pintype "passive"))
    )
    (net (code "107") (name "unconnected-(U_C1-GPIO-Pad159)") (class "Default")
      (node (ref "U_C1") (pin "159") (pinfunction "GPIO_159") (pintype "passive"))
    )
    (net (code "108") (name "unconnected-(U_C1-GPIO-Pad160)") (class "Default")
      (node (ref "U_C1") (pin "160") (pinfunction "GPIO_160") (pintype "passive"))
    )
    (net (code "109") (name "unconnected-(U_C1-GPIO-Pad161)") (class "Default")
      (node (ref "U_C1") (pin "161") (pinfunction "GPIO_161") (pintype "passive"))
    )
    (net (code "110") (name "unconnected-(U_C1-GPIO-Pad162)") (class "Default")
      (node (ref "U_C1") (pin "162") (pinfunction "GPIO_162") (pintype "passive"))
    )
    (net (code "111") (name "unconnected-(U_C1-GPIO-Pad163)") (class "Default")
      (node (ref "U_C1") (pin "163") (pinfunction "GPIO_163") (pintype "passive"))
    )
    (net (code "112") (name "unconnected-(U_C1-GPIO-Pad164)") (class "Default")
      (node (ref "U_C1") (pin "164") (pinfunction "GPIO_164") (pintype "passive"))
    )
    (net (code "113") (name "unconnected-(U_C1-GPIO-Pad165)") (class "Default")
      (node (ref "U_C1") (pin "165") (pinfunction "GPIO_165") (pintype "passive"))
    )
    (net (code "114") (name "unconnected-(U_C1-GPIO-Pad166)") (class "Default")
      (node (ref "U_C1") (pin "166") (pinfunction "GPIO_166") (pintype "passive"))
    )
    (net (code "115") (name "unconnected-(U_C1-GPIO-Pad167)") (class "Default")
      (node (ref "U_C1") (pin "167") (pinfunction "GPIO_167") (pintype "passive"))
    )
    (net (code "116") (name "unconnected-(U_C1-GPIO-Pad168)") (class "Default")
      (node (ref "U_C1") (pin "168") (pinfunction "GPIO_168") (pintype "passive"))
    )
    (net (code "117") (name "unconnected-(U_C1-GPIO-Pad169)") (class "Default")
      (node (ref "U_C1") (pin "169") (pinfunction "GPIO_169") (pintype "passive"))
    )
    (net (code "118") (name "unconnected-(U_C1-GPIO-Pad170)") (class "Default")
      (node (ref "U_C1") (pin "170") (pinfunction "GPIO_170") (pintype "passive"))
    )
    (net (code "119") (name "unconnected-(U_C1-GPIO_(McBSP-MFSRA)-Pad110)") (class "Default")
      (node (ref "U_C1") (pin "110") (pinfunction "GPIO_(McBSP-MFSRA)_110") (pintype "passive"))
    )
    (net (code "120") (name "unconnected-(U_C1-I2CSCLA-Pad87)") (class "Default")
      (node (ref "U_C1") (pin "87") (pinfunction "I2CSCLA_87") (pintype "passive"))
    )
    (net (code "121") (name "unconnected-(U_C1-I2CSDAA-Pad85)") (class "Default")
      (node (ref "U_C1") (pin "85") (pinfunction "I2CSDAA_85") (pintype "passive"))
    )
    (net (code "122") (name "unconnected-(U_C1-PWM5A-Pad57)") (class "Default")
      (node (ref "U_C1") (pin "57") (pinfunction "PWM5A_57") (pintype "passive"))
    )
    (net (code "123") (name "unconnected-(U_C1-PWM5B-Pad59)") (class "Default")
      (node (ref "U_C1") (pin "59") (pinfunction "PWM5B_59") (pintype "passive"))
    )
    (net (code "124") (name "unconnected-(U_C1-PWM6A-Pad61)") (class "Default")
      (node (ref "U_C1") (pin "61") (pinfunction "PWM6A_61") (pintype "passive"))
    )
    (net (code "125") (name "unconnected-(U_C1-PWM6B-Pad63)") (class "Default")
      (node (ref "U_C1") (pin "63") (pinfunction "PWM6B_63") (pintype "passive"))
    )
    (net (code "126") (name "unconnected-(U_C1-PWM7A{slash}TZI-Pad58)") (class "Default")
      (node (ref "U_C1") (pin "58") (pinfunction "PWM7A/TZI_58") (pintype "passive"))
    )
    (net (code "127") (name "unconnected-(U_C1-PWM7B{slash}TZ2-Pad60)") (class "Default")
      (node (ref "U_C1") (pin "60") (pinfunction "PWM7B/TZ2_60") (pintype "passive"))
    )
    (net (code "128") (name "unconnected-(U_C1-PWM8A{slash}TZ3-Pad62)") (class "Default")
      (node (ref "U_C1") (pin "62") (pinfunction "PWM8A/TZ3_62") (pintype "passive"))
    )
    (net (code "129") (name "unconnected-(U_C1-PWM8B{slash}TZ4-Pad64)") (class "Default")
      (node (ref "U_C1") (pin "64") (pinfunction "PWM8B/TZ4_64") (pintype "passive"))
    )
    (net (code "130") (name "unconnected-(U_C1-QEP1A_(McBSP-MDXA)-Pad68)") (class "Default")
      (node (ref "U_C1") (pin "68") (pinfunction "QEP1A_(McBSP-MDXA)_68") (pintype "passive"))
    )
    (net (code "131") (name "unconnected-(U_C1-QEP1B_(McBSP-MDRA)-Pad70)") (class "Default")
      (node (ref "U_C1") (pin "70") (pinfunction "QEP1B_(McBSP-MDRA)_70") (pintype "passive"))
    )
    (net (code "132") (name "unconnected-(U_C1-QEP1I_(McBSP-MCLKXA)-Pad74)") (class "Default")
      (node (ref "U_C1") (pin "74") (pinfunction "QEP1I_(McBSP-MCLKXA)_74") (pintype "passive"))
    )
    (net (code "133") (name "unconnected-(U_C1-QEP1S_(McBSP-MFSXA)-Pad72)") (class "Default")
      (node (ref "U_C1") (pin "72") (pinfunction "QEP1S_(McBSP-MFSXA)_72") (pintype "passive"))
    )
    (net (code "134") (name "unconnected-(U_C1-QEP2A_or_GPIO-Pad100)") (class "Default")
      (node (ref "U_C1") (pin "100") (pinfunction "QEP2A_or_GPIO_100") (pintype "passive"))
    )
    (net (code "135") (name "unconnected-(U_C1-QEP2A_or_GPIO-Pad102)") (class "Default")
      (node (ref "U_C1") (pin "102") (pinfunction "QEP2A_or_GPIO_102") (pintype "passive"))
    )
    (net (code "136") (name "unconnected-(U_C1-QEP2A_or_GPIO-Pad104)") (class "Default")
      (node (ref "U_C1") (pin "104") (pinfunction "QEP2A_or_GPIO_104") (pintype "passive"))
    )
    (net (code "137") (name "unconnected-(U_C1-QEP2A_or_GPIO-Pad106)") (class "Default")
      (node (ref "U_C1") (pin "106") (pinfunction "QEP2A_or_GPIO_106") (pintype "passive"))
    )
    (net (code "138") (name "unconnected-(U_C1-RESET(ACTIVE_LOW)-Pad120)") (class "Default")
      (node (ref "U_C1") (pin "120") (pinfunction "RESET(ACTIVE_LOW)_120") (pintype "passive"))
    )
    (net (code "139") (name "unconnected-(U_C1-Rsv-Pad32)") (class "Default")
      (node (ref "U_C1") (pin "32") (pinfunction "Rsv_32") (pintype "passive"))
    )
    (net (code "140") (name "unconnected-(U_C1-Rsv-Pad41)") (class "Default")
      (node (ref "U_C1") (pin "41") (pinfunction "Rsv_41") (pintype "passive"))
    )
    (net (code "141") (name "unconnected-(U_C1-Rsv-Pad44)") (class "Default")
      (node (ref "U_C1") (pin "44") (pinfunction "Rsv_44") (pintype "passive"))
    )
    (net (code "142") (name "unconnected-(U_C1-Rsv-Pad66)") (class "Default")
      (node (ref "U_C1") (pin "66") (pinfunction "Rsv_66") (pintype "passive"))
    )
    (net (code "143") (name "unconnected-(U_C1-Rsv-Pad113)") (class "Default")
      (node (ref "U_C1") (pin "113") (pinfunction "Rsv_113") (pintype "passive"))
    )
    (net (code "144") (name "unconnected-(U_C1-Rsv-Pad114)") (class "Default")
      (node (ref "U_C1") (pin "114") (pinfunction "Rsv_114") (pintype "passive"))
    )
    (net (code "145") (name "unconnected-(U_C1-Rsv-Pad115)") (class "Default")
      (node (ref "U_C1") (pin "115") (pinfunction "Rsv_115") (pintype "passive"))
    )
    (net (code "146") (name "unconnected-(U_C1-Rsv-Pad116)") (class "Default")
      (node (ref "U_C1") (pin "116") (pinfunction "Rsv_116") (pintype "passive"))
    )
    (net (code "147") (name "unconnected-(U_C1-Rsv-Pad117)") (class "Default")
      (node (ref "U_C1") (pin "117") (pinfunction "Rsv_117") (pintype "passive"))
    )
    (net (code "148") (name "unconnected-(U_C1-Rsv-Pad118)") (class "Default")
      (node (ref "U_C1") (pin "118") (pinfunction "Rsv_118") (pintype "passive"))
    )
    (net (code "149") (name "unconnected-(U_C1-Rsv-Pad119)") (class "Default")
      (node (ref "U_C1") (pin "119") (pinfunction "Rsv_119") (pintype "passive"))
    )
    (net (code "150") (name "unconnected-(U_C1-Rsv-Pad136)") (class "Default")
      (node (ref "U_C1") (pin "136") (pinfunction "Rsv_136") (pintype "passive"))
    )
    (net (code "151") (name "unconnected-(U_C1-Rsv-Pad171)") (class "Default")
      (node (ref "U_C1") (pin "171") (pinfunction "Rsv_171") (pintype "passive"))
    )
    (net (code "152") (name "unconnected-(U_C1-Rsv-Pad172)") (class "Default")
      (node (ref "U_C1") (pin "172") (pinfunction "Rsv_172") (pintype "passive"))
    )
    (net (code "153") (name "unconnected-(U_C1-Rsv-Pad173)") (class "Default")
      (node (ref "U_C1") (pin "173") (pinfunction "Rsv_173") (pintype "passive"))
    )
    (net (code "154") (name "unconnected-(U_C1-Rsv-Pad174)") (class "Default")
      (node (ref "U_C1") (pin "174") (pinfunction "Rsv_174") (pintype "passive"))
    )
    (net (code "155") (name "unconnected-(U_C1-Rsv-Pad175)") (class "Default")
      (node (ref "U_C1") (pin "175") (pinfunction "Rsv_175") (pintype "passive"))
    )
    (net (code "156") (name "unconnected-(U_C1-Rsv-Pad176)") (class "Default")
      (node (ref "U_C1") (pin "176") (pinfunction "Rsv_176") (pintype "passive"))
    )
    (net (code "157") (name "unconnected-(U_C1-Rsv-Pad177)") (class "Default")
      (node (ref "U_C1") (pin "177") (pinfunction "Rsv_177") (pintype "passive"))
    )
    (net (code "158") (name "unconnected-(U_C1-Rsv-Pad178)") (class "Default")
      (node (ref "U_C1") (pin "178") (pinfunction "Rsv_178") (pintype "passive"))
    )
    (net (code "159") (name "unconnected-(U_C1-SCIRXA{slash}UARTRXA-Pad76)") (class "Default")
      (node (ref "U_C1") (pin "76") (pinfunction "SCIRXA/UARTRXA_76") (pintype "passive"))
    )
    (net (code "160") (name "unconnected-(U_C1-SCITXA{slash}UARTTXA-Pad78)") (class "Default")
      (node (ref "U_C1") (pin "78") (pinfunction "SCITXA/UARTTXA_78") (pintype "passive"))
    )
    (net (code "161") (name "unconnected-(U_C1-SD-C1-Pad101)") (class "Default")
      (node (ref "U_C1") (pin "101") (pinfunction "SD-C1_101") (pintype "passive"))
    )
    (net (code "162") (name "unconnected-(U_C1-SD-C2-Pad105)") (class "Default")
      (node (ref "U_C1") (pin "105") (pinfunction "SD-C2_105") (pintype "passive"))
    )
    (net (code "163") (name "unconnected-(U_C1-SD-C3-Pad109)") (class "Default")
      (node (ref "U_C1") (pin "109") (pinfunction "SD-C3_109") (pintype "passive"))
    )
    (net (code "164") (name "unconnected-(U_C1-SD-D1-Pad99)") (class "Default")
      (node (ref "U_C1") (pin "99") (pinfunction "SD-D1_99") (pintype "passive"))
    )
    (net (code "165") (name "unconnected-(U_C1-SD-D2-Pad103)") (class "Default")
      (node (ref "U_C1") (pin "103") (pinfunction "SD-D2_103") (pintype "passive"))
    )
    (net (code "166") (name "unconnected-(U_C1-SD-D3-Pad107)") (class "Default")
      (node (ref "U_C1") (pin "107") (pinfunction "SD-D3_107") (pintype "passive"))
    )
    (net (code "167") (name "unconnected-(U_C1-SPICLKA-Pad71)") (class "Default")
      (node (ref "U_C1") (pin "71") (pinfunction "SPICLKA_71") (pintype "passive"))
    )
    (net (code "168") (name "unconnected-(U_C1-SPISIMOA-Pad67)") (class "Default")
      (node (ref "U_C1") (pin "67") (pinfunction "SPISIMOA_67") (pintype "passive"))
    )
    (net (code "169") (name "unconnected-(U_C1-SPISOMIA-Pad69)") (class "Default")
      (node (ref "U_C1") (pin "69") (pinfunction "SPISOMIA_69") (pintype "passive"))
    )
    (net (code "170") (name "unconnected-(U_C1-SPISTEA-Pad73)") (class "Default")
      (node (ref "U_C1") (pin "73") (pinfunction "SPISTEA_73") (pintype "passive"))
    )
    (net (code "171") (name "unconnected-(U_C1-VREFHI-Pad45)") (class "Default")
      (node (ref "U_C1") (pin "45") (pinfunction "VREFHI_45") (pintype "passive"))
    )
    (net (code "172") (name "unconnected-(U_C1-VREFLO-Pad43)") (class "Default")
      (node (ref "U_C1") (pin "43") (pinfunction "VREFLO_43") (pintype "passive"))
    )
  )
)
